# Power.net
KiCad netlist of a schematic drawn in Altium Designer
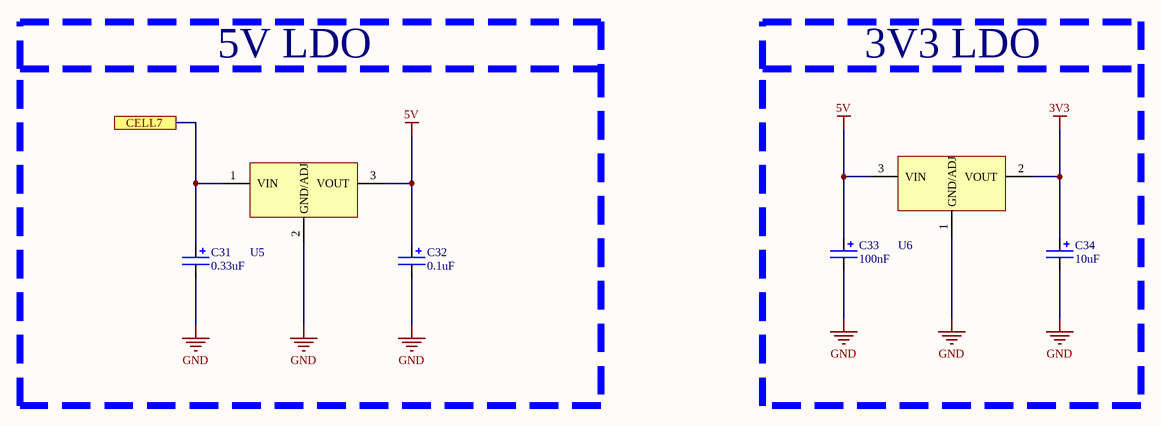
[diagram p0: Power.SchDoc]

(export (version "E")
  (design (tool "Eeschema 10.0.6"))
  (components
    (comp (ref "C31")
      (value "0.33uF")
      (footprint "CAP 0603")
      (description "Multilayer Ceramic Capacitor")
      (fields (field (name "Comment") "CAP 0603"))
      (libsource (lib "Kaptanyums Lib") (part "CAP 0603"))
    )
    (comp (ref "C32")
      (value "0.1uF")
      (footprint "CAP 0603")
      (description "Multilayer Ceramic Capacitor")
      (fields (field (name "Comment") "CAP 0603"))
      (libsource (lib "Kaptanyums Lib") (part "CAP 0603"))
    )
    (comp (ref "C33")
      (value "100nF")
      (footprint "CAP 0603")
      (description "Multilayer Ceramic Capacitor")
      (fields (field (name "Comment") "CAP 0603"))
      (libsource (lib "Kaptanyums Lib") (part "CAP 0603"))
    )
    (comp (ref "C34")
      (value "10uF")
      (footprint "CAP 0603")
      (description "Multilayer Ceramic Capacitor")
      (fields (field (name "Comment") "CAP 0603"))
      (libsource (lib "Kaptanyums Lib") (part "CAP 0603"))
    )
    (comp (ref "U5")
      (value "LM7805MPX")
      (footprint "SOT223-3")
      (description "Regulator Linear")
      (libsource (lib "Kaptanyums Lib") (part "LM7805MPX"))
    )
    (comp (ref "U6")
      (value "LD1117AS33")
      (footprint "SOT223-3")
      (description "Regulator Linear")
      (libsource (lib "Kaptanyums Lib") (part "LD1117AS33"))
    )
  )
  (nets
    (net (code "1") (name "/CELL7") (class "Default")
      (node (ref "C31") (pin "1") (pinfunction "1_1") (pintype "passive"))
      (node (ref "U5") (pin "1") (pinfunction "VIN_1") (pintype "passive"))
    )
    (net (code "2") (name "3V3") (class "Default")
      (node (ref "C34") (pin "1") (pinfunction "1_1") (pintype "passive"))
      (node (ref "U6") (pin "2") (pinfunction "VOUT_2") (pintype "passive"))
    )
    (net (code "3") (name "5V") (class "Default")
      (node (ref "C32") (pin "1") (pinfunction "1_1") (pintype "passive"))
      (node (ref "C33") (pin "1") (pinfunction "1_1") (pintype "passive"))
      (node (ref "U5") (pin "3") (pinfunction "VOUT_3") (pintype "passive"))
      (node (ref "U6") (pin "3") (pinfunction "VIN_3") (pintype "passive"))
    )
    (net (code "4") (name "GND") (class "Default")
      (node (ref "C31") (pin "2") (pinfunction "2_2") (pintype "passive"))
      (node (ref "C32") (pin "2") (pinfunction "2_2") (pintype "passive"))
      (node (ref "C33") (pin "2") (pinfunction "2_2") (pintype "passive"))
      (node (ref "C34") (pin "2") (pinfunction "2_2") (pintype "passive"))
      (node (ref "U5") (pin "2") (pinfunction "GND/ADJ_2") (pintype "passive"))
      (node (ref "U6") (pin "1") (pinfunction "GND/ADJ_1") (pintype "passive"))
    )
  )
)
